# 4_digit_7_seg.net
KiCad netlist of a schematic drawn in Altium Designer
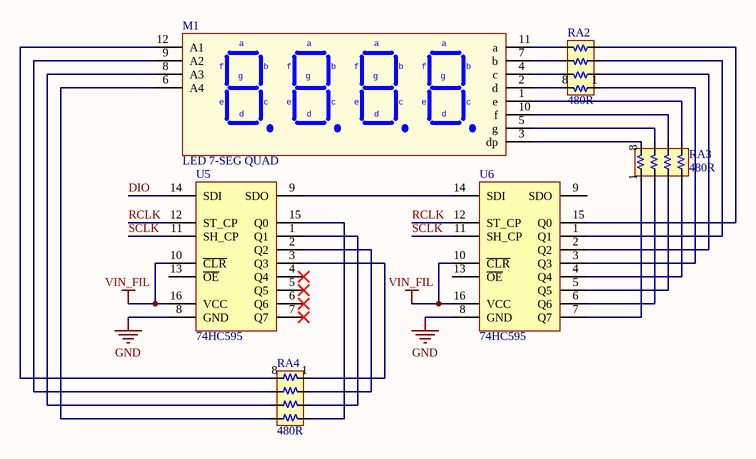
[diagram p0: 4_digit_7_seg.SchDoc]

(export (version "E")
  (design (tool "Eeschema 10.0.6"))
  (components
    (comp (ref "M1")
      (value "LED 7-SEG QUAD")
      (footprint "LED/7SEG/0.56/QUAD")
      (description "LED 7-SEG 0.56 QUAD RED")
      (libsource (lib "chipfc_altium_libs") (part "LED 7-SEG QUAD"))
    )
    (comp (ref "RA2")
      (value "480R")
      (footprint "RA4 1206 (3216)")
      (description "Resistor Array 4")
      (libsource (lib "") (part "Resistor Array 4_1"))
    )
    (comp (ref "RA3")
      (value "480R")
      (footprint "RA4 1206 (3216)")
      (description "Resistor Array 4")
      (libsource (lib "") (part "Resistor Array 4_2"))
    )
    (comp (ref "RA4")
      (value "480R")
      (footprint "RA4 1206 (3216)")
      (description "Resistor Array 4")
      (libsource (lib "chipfc_altium_libs") (part "Resistor Array 4"))
    )
    (comp (ref "U5")
      (value "74HC595")
      (footprint "SOIC-16")
      (description "8-bit serial-in, serial or parallel-out  shift register with output latches;  3-state")
      (libsource (lib "chipfc_altium_libs") (part "74HC595"))
    )
    (comp (ref "U6")
      (value "74HC595")
      (footprint "SOIC-16")
      (description "8-bit serial-in, serial or parallel-out  shift register with output latches;  3-state")
      (libsource (lib "chipfc_altium_libs") (part "74HC595"))
    )
  )
  (nets
    (net (code "1") (name "/DIO") (class "Default")
      (node (ref "U5") (pin "14") (pinfunction "SDI_14") (pintype "passive"))
    )
    (net (code "2") (name "/RCLK") (class "Default")
      (node (ref "U5") (pin "12") (pinfunction "ST_CP_12") (pintype "passive"))
      (node (ref "U6") (pin "12") (pinfunction "ST_CP_12") (pintype "passive"))
    )
    (net (code "3") (name "/SCLK") (class "Default")
      (node (ref "U5") (pin "11") (pinfunction "SH_CP_11") (pintype "passive"))
      (node (ref "U6") (pin "11") (pinfunction "SH_CP_11") (pintype "passive"))
    )
    (net (code "4") (name "GND") (class "Default")
      (node (ref "U5") (pin "8") (pinfunction "GND_8") (pintype "passive"))
      (node (ref "U6") (pin "8") (pinfunction "GND_8") (pintype "passive"))
    )
    (net (code "5") (name "Net-(M1-A1)") (class "Default")
      (node (ref "M1") (pin "12") (pinfunction "A1_12") (pintype "passive"))
      (node (ref "RA4") (pin "8") (pinfunction "8_8") (pintype "passive"))
    )
    (net (code "6") (name "Net-(M1-A2)") (class "Default")
      (node (ref "M1") (pin "9") (pinfunction "A2_9") (pintype "passive"))
      (node (ref "RA4") (pin "7") (pinfunction "7_7") (pintype "passive"))
    )
    (net (code "7") (name "Net-(M1-A3)") (class "Default")
      (node (ref "M1") (pin "8") (pinfunction "A3_8") (pintype "passive"))
      (node (ref "RA4") (pin "6") (pinfunction "6_6") (pintype "passive"))
    )
    (net (code "8") (name "Net-(M1-A4)") (class "Default")
      (node (ref "M1") (pin "6") (pinfunction "A4_6") (pintype "passive"))
      (node (ref "RA4") (pin "5") (pinfunction "5_5") (pintype "passive"))
    )
    (net (code "9") (name "Net-(M1-a)") (class "Default")
      (node (ref "M1") (pin "11") (pinfunction "a_11") (pintype "passive"))
      (node (ref "RA2") (pin "5") (pinfunction "5_5") (pintype "passive"))
    )
    (net (code "10") (name "Net-(M1-b)") (class "Default")
      (node (ref "M1") (pin "7") (pinfunction "b_7") (pintype "passive"))
      (node (ref "RA2") (pin "6") (pinfunction "6_6") (pintype "passive"))
    )
    (net (code "11") (name "Net-(M1-c)") (class "Default")
      (node (ref "M1") (pin "4") (pinfunction "c_4") (pintype "passive"))
      (node (ref "RA2") (pin "7") (pinfunction "7_7") (pintype "passive"))
    )
    (net (code "12") (name "Net-(M1-d)") (class "Default")
      (node (ref "M1") (pin "2") (pinfunction "d_2") (pintype "passive"))
      (node (ref "RA2") (pin "8") (pinfunction "8_8") (pintype "passive"))
    )
    (net (code "13") (name "Net-(M1-dp)") (class "Default")
      (node (ref "M1") (pin "3") (pinfunction "dp_3") (pintype "passive"))
      (node (ref "RA3") (pin "8") (pinfunction "8_8") (pintype "passive"))
    )
    (net (code "14") (name "Net-(M1-e)") (class "Default")
      (node (ref "M1") (pin "1") (pinfunction "e_1") (pintype "passive"))
      (node (ref "RA3") (pin "5") (pinfunction "5_5") (pintype "passive"))
    )
    (net (code "15") (name "Net-(M1-f)") (class "Default")
      (node (ref "M1") (pin "10") (pinfunction "f_10") (pintype "passive"))
      (node (ref "RA3") (pin "6") (pinfunction "6_6") (pintype "passive"))
    )
    (net (code "16") (name "Net-(M1-g)") (class "Default")
      (node (ref "M1") (pin "5") (pinfunction "g_5") (pintype "passive"))
      (node (ref "RA3") (pin "7") (pinfunction "7_7") (pintype "passive"))
    )
    (net (code "17") (name "Net-(U5-Q0)") (class "Default")
      (node (ref "RA4") (pin "4") (pinfunction "4_4") (pintype "passive"))
      (node (ref "U5") (pin "15") (pinfunction "Q0_15") (pintype "passive"))
    )
    (net (code "18") (name "Net-(U5-Q1)") (class "Default")
      (node (ref "RA4") (pin "3") (pinfunction "3_3") (pintype "passive"))
      (node (ref "U5") (pin "1") (pinfunction "Q1_1") (pintype "passive"))
    )
    (net (code "19") (name "Net-(U5-Q2)") (class "Default")
      (node (ref "RA4") (pin "2") (pinfunction "2_2") (pintype "passive"))
      (node (ref "U5") (pin "2") (pinfunction "Q2_2") (pintype "passive"))
    )
    (net (code "20") (name "Net-(U5-Q3)") (class "Default")
      (node (ref "RA4") (pin "1") (pinfunction "1_1") (pintype "passive"))
      (node (ref "U5") (pin "3") (pinfunction "Q3_3") (pintype "passive"))
    )
    (net (code "21") (name "Net-(U5-SDO)") (class "Default")
      (node (ref "U5") (pin "9") (pinfunction "SDO_9") (pintype "passive"))
      (node (ref "U6") (pin "14") (pinfunction "SDI_14") (pintype "passive"))
    )
    (net (code "22") (name "Net-(U6-Q0)") (class "Default")
      (node (ref "RA2") (pin "4") (pinfunction "4_4") (pintype "passive"))
      (node (ref "U6") (pin "15") (pinfunction "Q0_15") (pintype "passive"))
    )
    (net (code "23") (name "Net-(U6-Q1)") (class "Default")
      (node (ref "RA2") (pin "3") (pinfunction "3_3") (pintype "passive"))
      (node (ref "U6") (pin "1") (pinfunction "Q1_1") (pintype "passive"))
    )
    (net (code "24") (name "Net-(U6-Q2)") (class "Default")
      (node (ref "RA2") (pin "2") (pinfunction "2_2") (pintype "passive"))
      (node (ref "U6") (pin "2") (pinfunction "Q2_2") (pintype "passive"))
    )
    (net (code "25") (name "Net-(U6-Q3)") (class "Default")
      (node (ref "RA2") (pin "1") (pinfunction "1_1") (pintype "passive"))
      (node (ref "U6") (pin "3") (pinfunction "Q3_3") (pintype "passive"))
    )
    (net (code "26") (name "Net-(U6-Q4)") (class "Default")
      (node (ref "RA3") (pin "4") (pinfunction "4_4") (pintype "passive"))
      (node (ref "U6") (pin "4") (pinfunction "Q4_4") (pintype "passive"))
    )
    (net (code "27") (name "Net-(U6-Q5)") (class "Default")
      (node (ref "RA3") (pin "3") (pinfunction "3_3") (pintype "passive"))
      (node (ref "U6") (pin "5") (pinfunction "Q5_5") (pintype "passive"))
    )
    (net (code "28") (name "Net-(U6-Q6)") (class "Default")
      (node (ref "RA3") (pin "2") (pinfunction "2_2") (pintype "passive"))
      (node (ref "U6") (pin "6") (pinfunction "Q6_6") (pintype "passive"))
    )
    (net (code "29") (name "Net-(U6-Q7)") (class "Default")
      (node (ref "RA3") (pin "1") (pinfunction "1_1") (pintype "passive"))
      (node (ref "U6") (pin "7") (pinfunction "Q7_7") (pintype "passive"))
    )
    (net (code "30") (name "VIN_FIL") (class "Default")
      (node (ref "U5") (pin "10") (pinfunction "~{CLR}_10") (pintype "passive"))
      (node (ref "U5") (pin "16") (pinfunction "VCC_16") (pintype "passive"))
      (node (ref "U6") (pin "10") (pinfunction "~{CLR}_10") (pintype "passive"))
      (node (ref "U6") (pin "16") (pinfunction "VCC_16") (pintype "passive"))
    )
    (net (code "31") (name "unconnected-(U5-Q4-Pad4)") (class "Default")
      (node (ref "U5") (pin "4") (pinfunction "Q4_4") (pintype "passive+no_connect"))
    )
    (net (code "32") (name "unconnected-(U5-Q5-Pad5)") (class "Default")
      (node (ref "U5") (pin "5") (pinfunction "Q5_5") (pintype "passive+no_connect"))
    )
    (net (code "33") (name "unconnected-(U5-Q6-Pad6)") (class "Default")
      (node (ref "U5") (pin "6") (pinfunction "Q6_6") (pintype "passive+no_connect"))
    )
    (net (code "34") (name "unconnected-(U5-Q7-Pad7)") (class "Default")
      (node (ref "U5") (pin "7") (pinfunction "Q7_7") (pintype "passive+no_connect"))
    )
    (net (code "35") (name "unconnected-(U5-~{OE}-Pad13)") (class "Default")
      (node (ref "U5") (pin "13") (pinfunction "~{OE}_13") (pintype "passive"))
    )
    (net (code "36") (name "unconnected-(U6-SDO-Pad9)") (class "Default")
      (node (ref "U6") (pin "9") (pinfunction "SDO_9") (pintype "passive"))
    )
    (net (code "37") (name "unconnected-(U6-~{OE}-Pad13)") (class "Default")
      (node (ref "U6") (pin "13") (pinfunction "~{OE}_13") (pintype "passive"))
    )
  )
)
